# USB_Dongle_Parem.net
KiCad netlist of a schematic drawn in EAGLE
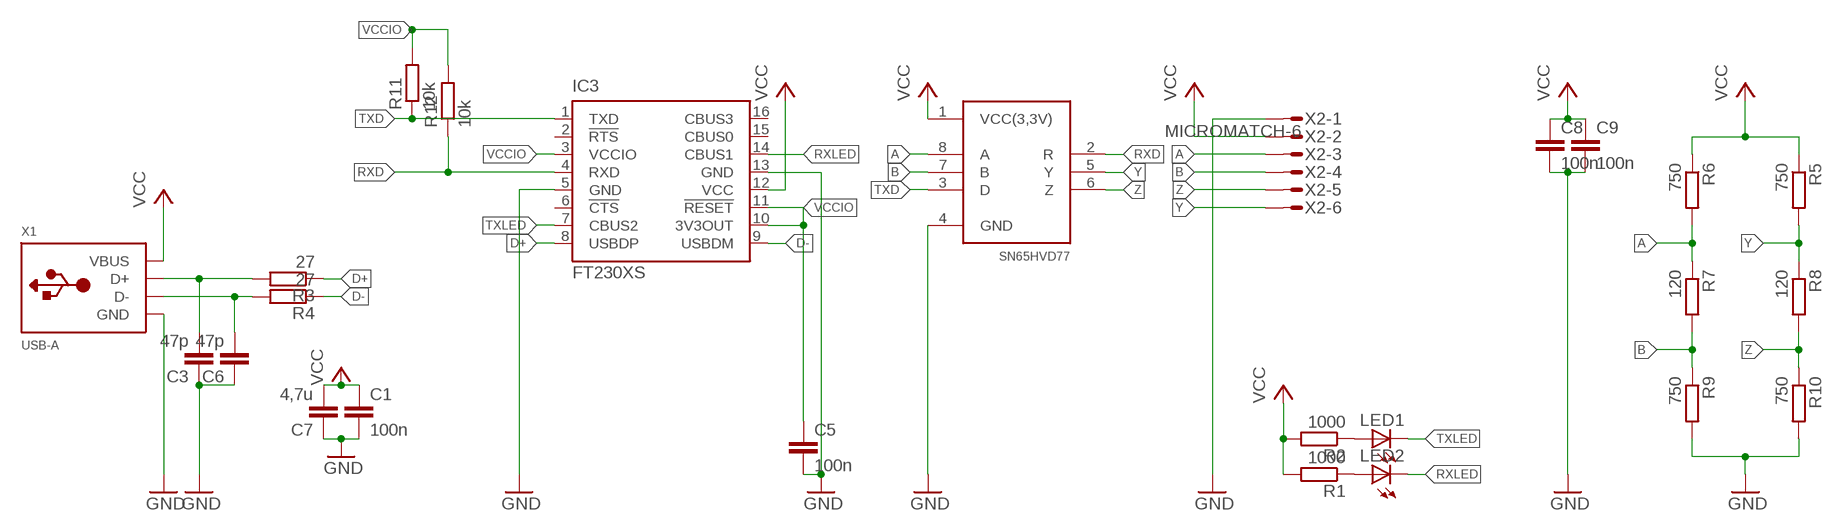
[diagram p0: schematic, sheet 1]

(export (version "E")
  (design (tool "Eeschema 10.0.6"))
  (components
    (comp (ref "C1")
      (value "100n")
      (footprint "eagle-import:C0603")
      (libsource (lib "eagle-import") (part "CC0603"))
    )
    (comp (ref "C3")
      (value "47p")
      (footprint "eagle-import:C0603")
      (libsource (lib "eagle-import") (part "CC0603"))
    )
    (comp (ref "C5")
      (value "100n")
      (footprint "eagle-import:C0603")
      (libsource (lib "eagle-import") (part "CC0603"))
    )
    (comp (ref "C6")
      (value "47p")
      (footprint "eagle-import:C0603")
      (libsource (lib "eagle-import") (part "CC0603"))
    )
    (comp (ref "C7")
      (value "4,7u")
      (footprint "eagle-import:C1206")
      (libsource (lib "eagle-import") (part "CC1206"))
    )
    (comp (ref "C8")
      (value "100n")
      (footprint "eagle-import:C0603")
      (libsource (lib "eagle-import") (part "CC0603"))
    )
    (comp (ref "C9")
      (value "100n")
      (footprint "eagle-import:C0603")
      (libsource (lib "eagle-import") (part "CC0603"))
    )
    (comp (ref "IC3")
      (value "FT230XS")
      (footprint "eagle-import:SSOP16")
      (libsource (lib "eagle-import") (part "FT230XS"))
    )
    (comp (ref "LED1")
      (value "LED_ESML0603")
      (footprint "eagle-import:LED_SML0603")
      (libsource (lib "eagle-import") (part "LED_ESML0603"))
    )
    (comp (ref "LED2")
      (value "LED_ESML0603")
      (footprint "eagle-import:LED_SML0603")
      (libsource (lib "eagle-import") (part "LED_ESML0603"))
    )
    (comp (ref "R1")
      (value "1000")
      (footprint "eagle-import:R0603")
      (libsource (lib "eagle-import") (part "R-EU_R0603"))
    )
    (comp (ref "R2")
      (value "1000")
      (footprint "eagle-import:R0603")
      (libsource (lib "eagle-import") (part "R-EU_R0603"))
    )
    (comp (ref "R3")
      (value "27")
      (footprint "eagle-import:R0603")
      (libsource (lib "eagle-import") (part "R-EU_R0603"))
    )
    (comp (ref "R4")
      (value "27")
      (footprint "eagle-import:R0603")
      (libsource (lib "eagle-import") (part "R-EU_R0603"))
    )
    (comp (ref "R5")
      (value "750")
      (footprint "eagle-import:R0603")
      (libsource (lib "eagle-import") (part "R-EU_R0603"))
    )
    (comp (ref "R6")
      (value "750")
      (footprint "eagle-import:R0603")
      (libsource (lib "eagle-import") (part "R-EU_R0603"))
    )
    (comp (ref "R7")
      (value "120")
      (footprint "eagle-import:R0603")
      (libsource (lib "eagle-import") (part "R-EU_R0603"))
    )
    (comp (ref "R8")
      (value "120")
      (footprint "eagle-import:R0603")
      (libsource (lib "eagle-import") (part "R-EU_R0603"))
    )
    (comp (ref "R9")
      (value "750")
      (footprint "eagle-import:R0603")
      (libsource (lib "eagle-import") (part "R-EU_R0603"))
    )
    (comp (ref "R10")
      (value "750")
      (footprint "eagle-import:R0603")
      (libsource (lib "eagle-import") (part "R-EU_R0603"))
    )
    (comp (ref "R11")
      (value "10k")
      (footprint "eagle-import:R0603")
      (libsource (lib "eagle-import") (part "R-EU_R0603"))
    )
    (comp (ref "R12")
      (value "10k")
      (footprint "eagle-import:R0603")
      (libsource (lib "eagle-import") (part "R-EU_R0603"))
    )
    (comp (ref "U$2")
      (value "SN65HVD77D")
      (footprint "eagle-import:SOIC-8")
      (libsource (lib "eagle-import") (part "SN65HVD77D"))
    )
    (comp (ref "X1")
      (value "USB-A")
      (footprint "eagle-import:MOLEX_480371000")
      (libsource (lib "eagle-import") (part "USB-A"))
    )
    (comp (ref "X2")
      (value "MICROMATCH-6")
      (footprint "eagle-import:MICROMATCH-6")
      (fields (field (name "MPN") "7-215464-6"))
      (libsource (lib "eagle-import") (part "MICROMATCH-6"))
    )
  )
  (nets
    (net (code "1") (name "A") (class "Default")
      (node (ref "R6") (pin "2") (pinfunction "2_2") (pintype "passive"))
      (node (ref "R7") (pin "1") (pinfunction "1_1") (pintype "passive"))
      (node (ref "U$2") (pin "8") (pinfunction "A_8") (pintype "bidirectional"))
      (node (ref "X2") (pin "3") (pinfunction "S_3") (pintype "passive"))
    )
    (net (code "2") (name "B") (class "Default")
      (node (ref "R7") (pin "2") (pinfunction "2_2") (pintype "passive"))
      (node (ref "R9") (pin "1") (pinfunction "1_1") (pintype "passive"))
      (node (ref "U$2") (pin "7") (pinfunction "B_7") (pintype "bidirectional"))
      (node (ref "X2") (pin "4") (pinfunction "S_4") (pintype "passive"))
    )
    (net (code "3") (name "D+") (class "Default")
      (node (ref "IC3") (pin "8") (pinfunction "USBDP_8") (pintype "input"))
      (node (ref "R3") (pin "1") (pinfunction "1_1") (pintype "passive"))
    )
    (net (code "4") (name "D-") (class "Default")
      (node (ref "IC3") (pin "9") (pinfunction "USBDM_9") (pintype "input"))
      (node (ref "R4") (pin "1") (pinfunction "1_1") (pintype "passive"))
    )
    (net (code "5") (name "GND") (class "Default")
      (node (ref "C1") (pin "2") (pinfunction "2_2") (pintype "passive"))
      (node (ref "C3") (pin "1") (pinfunction "1_1") (pintype "passive"))
      (node (ref "C5") (pin "2") (pinfunction "2_2") (pintype "passive"))
      (node (ref "C6") (pin "1") (pinfunction "1_1") (pintype "passive"))
      (node (ref "C7") (pin "1") (pinfunction "1_1") (pintype "passive"))
      (node (ref "C8") (pin "2") (pinfunction "2_2") (pintype "passive"))
      (node (ref "C9") (pin "2") (pinfunction "2_2") (pintype "passive"))
      (node (ref "IC3") (pin "13") (pinfunction "GND_13") (pintype "power_in"))
      (node (ref "IC3") (pin "5") (pinfunction "GND_5") (pintype "power_in"))
      (node (ref "R10") (pin "2") (pinfunction "2_2") (pintype "passive"))
      (node (ref "R9") (pin "2") (pinfunction "2_2") (pintype "passive"))
      (node (ref "U$2") (pin "4") (pinfunction "GND_4") (pintype "bidirectional"))
      (node (ref "X1") (pin "4") (pinfunction "GND_4") (pintype "power_in"))
      (node (ref "X2") (pin "1") (pinfunction "S_1") (pintype "passive"))
    )
    (net (code "6") (name "Net-(LED1-PadA)") (class "Default")
      (node (ref "LED1") (pin "A") (pinfunction "A_A") (pintype "passive"))
      (node (ref "R2") (pin "1") (pinfunction "1_1") (pintype "passive"))
    )
    (net (code "7") (name "Net-(LED2-PadA)") (class "Default")
      (node (ref "LED2") (pin "A") (pinfunction "A_A") (pintype "passive"))
      (node (ref "R1") (pin "1") (pinfunction "1_1") (pintype "passive"))
    )
    (net (code "8") (name "Net-(X1-D+)") (class "Default")
      (node (ref "C3") (pin "2") (pinfunction "2_2") (pintype "passive"))
      (node (ref "R3") (pin "2") (pinfunction "2_2") (pintype "passive"))
      (node (ref "X1") (pin "3") (pinfunction "D+_3") (pintype "bidirectional"))
    )
    (net (code "9") (name "Net-(X1-D-)") (class "Default")
      (node (ref "C6") (pin "2") (pinfunction "2_2") (pintype "passive"))
      (node (ref "R4") (pin "2") (pinfunction "2_2") (pintype "passive"))
      (node (ref "X1") (pin "2") (pinfunction "D-_2") (pintype "bidirectional"))
    )
    (net (code "10") (name "RXD") (class "Default")
      (node (ref "IC3") (pin "4") (pinfunction "RXD_4") (pintype "input"))
      (node (ref "R12") (pin "1") (pinfunction "1_1") (pintype "passive"))
      (node (ref "U$2") (pin "2") (pinfunction "R_2") (pintype "bidirectional"))
    )
    (net (code "11") (name "RXLED") (class "Default")
      (node (ref "IC3") (pin "14") (pinfunction "CBUS1_14") (pintype "bidirectional"))
      (node (ref "LED2") (pin "C") (pinfunction "C_C") (pintype "passive"))
    )
    (net (code "12") (name "TXD") (class "Default")
      (node (ref "IC3") (pin "1") (pinfunction "TXD_1") (pintype "output"))
      (node (ref "R11") (pin "1") (pinfunction "1_1") (pintype "passive"))
      (node (ref "U$2") (pin "3") (pinfunction "D_3") (pintype "bidirectional"))
    )
    (net (code "13") (name "TXLED") (class "Default")
      (node (ref "IC3") (pin "7") (pinfunction "CBUS2_7") (pintype "bidirectional"))
      (node (ref "LED1") (pin "C") (pinfunction "C_C") (pintype "passive"))
    )
    (net (code "14") (name "VCC") (class "Default")
      (node (ref "C1") (pin "1") (pinfunction "1_1") (pintype "passive"))
      (node (ref "C7") (pin "2") (pinfunction "2_2") (pintype "passive"))
      (node (ref "C8") (pin "1") (pinfunction "1_1") (pintype "passive"))
      (node (ref "C9") (pin "1") (pinfunction "1_1") (pintype "passive"))
      (node (ref "IC3") (pin "12") (pinfunction "VCC_12") (pintype "power_in"))
      (node (ref "R1") (pin "2") (pinfunction "2_2") (pintype "passive"))
      (node (ref "R2") (pin "2") (pinfunction "2_2") (pintype "passive"))
      (node (ref "R5") (pin "1") (pinfunction "1_1") (pintype "passive"))
      (node (ref "R6") (pin "1") (pinfunction "1_1") (pintype "passive"))
      (node (ref "U$2") (pin "1") (pinfunction "VCC(3,3V)_1") (pintype "bidirectional"))
      (node (ref "X1") (pin "1") (pinfunction "VBUS_1") (pintype "power_in"))
      (node (ref "X2") (pin "2") (pinfunction "S_2") (pintype "passive"))
    )
    (net (code "15") (name "VCCIO") (class "Default")
      (node (ref "C5") (pin "1") (pinfunction "1_1") (pintype "passive"))
      (node (ref "IC3") (pin "10") (pinfunction "3V3OUT_10") (pintype "output"))
      (node (ref "IC3") (pin "11") (pinfunction "~{RESET}_11") (pintype "input"))
      (node (ref "IC3") (pin "3") (pinfunction "VCCIO_3") (pintype "power_in"))
      (node (ref "R11") (pin "2") (pinfunction "2_2") (pintype "passive"))
      (node (ref "R12") (pin "2") (pinfunction "2_2") (pintype "passive"))
    )
    (net (code "16") (name "Y") (class "Default")
      (node (ref "R5") (pin "2") (pinfunction "2_2") (pintype "passive"))
      (node (ref "R8") (pin "1") (pinfunction "1_1") (pintype "passive"))
      (node (ref "U$2") (pin "5") (pinfunction "Y_5") (pintype "bidirectional"))
      (node (ref "X2") (pin "6") (pinfunction "S_6") (pintype "passive"))
    )
    (net (code "17") (name "Z") (class "Default")
      (node (ref "R10") (pin "1") (pinfunction "1_1") (pintype "passive"))
      (node (ref "R8") (pin "2") (pinfunction "2_2") (pintype "passive"))
      (node (ref "U$2") (pin "6") (pinfunction "Z_6") (pintype "bidirectional"))
      (node (ref "X2") (pin "5") (pinfunction "S_5") (pintype "passive"))
    )
    (net (code "18") (name "unconnected-(IC3-CBUS0-Pad15)") (class "Default")
      (node (ref "IC3") (pin "15") (pinfunction "CBUS0_15") (pintype "bidirectional"))
    )
    (net (code "19") (name "unconnected-(IC3-CBUS3-Pad16)") (class "Default")
      (node (ref "IC3") (pin "16") (pinfunction "CBUS3_16") (pintype "bidirectional"))
    )
    (net (code "20") (name "unconnected-(IC3-~{CTS}-Pad6)") (class "Default")
      (node (ref "IC3") (pin "6") (pinfunction "~{CTS}_6") (pintype "input"))
    )
    (net (code "21") (name "unconnected-(IC3-~{RTS}-Pad2)") (class "Default")
      (node (ref "IC3") (pin "2") (pinfunction "~{RTS}_2") (pintype "output"))
    )
  )
)
